# Channel.net
KiCad netlist of a schematic drawn in Altium Designer
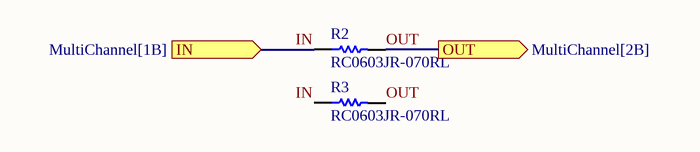
[diagram p0: Channel.SchDoc]

(export (version "E")
  (design (tool "Eeschema 10.0.6"))
  (components
    (comp (ref "R2")
      (value "RC0603JR-070RL")
      (footprint "RESC1608X55X25ML10T15")
      (description "Chip Resistor, 0 Ohm, +/- 5%, 0.1 W, -55 to 155 degC, 0603 (1608 Metric), RoHS, Tape and Reel")
      (fields (field (name "TOLERANCE") "5%") (field (name "MANUFACTURER") "Yageo"))
      (libsource (lib "Altium Content Vault") (part "RES-2"))
    )
    (comp (ref "R3")
      (value "RC0603JR-070RL")
      (footprint "RESC1608X55X25ML10T15")
      (description "Chip Resistor, 0 Ohm, +/- 5%, 0.1 W, -55 to 155 degC, 0603 (1608 Metric), RoHS, Tape and Reel")
      (fields (field (name "TOLERANCE") "5%") (field (name "MANUFACTURER") "Yageo"))
      (libsource (lib "Altium Content Vault") (part "RES-2"))
    )
  )
  (nets
    (net (code "1") (name "/IN") (class "Default")
      (node (ref "R2") (pin "1") (pinfunction "1_1") (pintype "passive"))
      (node (ref "R3") (pin "1") (pinfunction "1_1") (pintype "passive"))
    )
    (net (code "2") (name "/OUT") (class "Default")
      (node (ref "R2") (pin "2") (pinfunction "2_2") (pintype "passive"))
      (node (ref "R3") (pin "2") (pinfunction "2_2") (pintype "passive"))
    )
  )
)
